# Power_Supply.net
KiCad netlist of a schematic drawn in Altium Designer
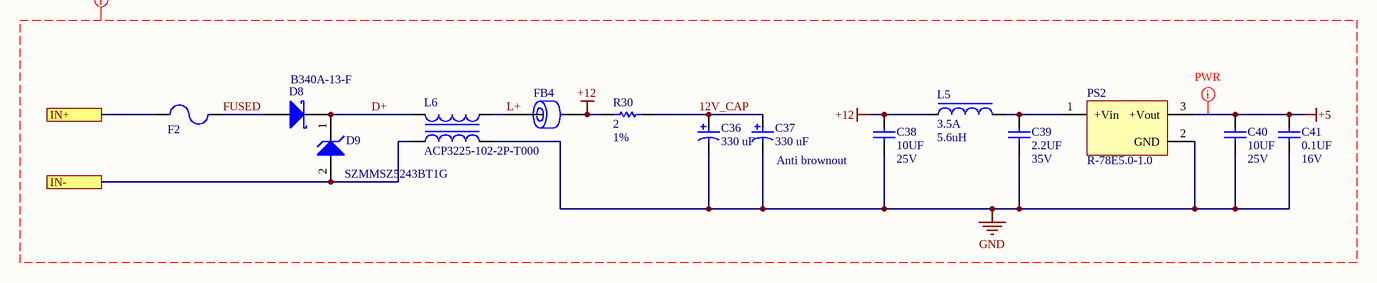
[diagram p0: Power Supply.SchDoc]

(export (version "E")
  (design (tool "Eeschema 10.0.6"))
  (components
    (comp (ref "C36")
      (value "UUD1V331MNL1GS")
      (footprint "NIC-CAPA2-10X10_V")
      (fields (field (name "MANUFACTURER") "Nichicon") (field (name "RATED CAPACITANCE") "330 uF"))
      (libsource (lib "AERO Parts") (part "UUD1V331MNL1GS"))
    )
    (comp (ref "C37")
      (value "UUD1V331MNL1GS")
      (footprint "NIC-CAPA2-10X10_V")
      (fields (field (name "MANUFACTURER") "Nichicon") (field (name "RATED CAPACITANCE") "330 uF"))
      (libsource (lib "AERO Parts") (part "UUD1V331MNL1GS"))
    )
    (comp (ref "C38")
      (value "CAP 0603 10UF 25V 20% X5R")
      (footprint "0603_CAP")
      (description "Capacitor Surface Mount 0603 Footprint 10UF 25V 20% Tolerance Ceramic X5R")
      (fields
        (field (name "VAL") "10UF")
        (field (name "VOL") "25V")
        (field (name "MANUFACTURER") "Various")
        (field (name "VOLTAGE") "25V")
      )
      (libsource (lib "Passive Components") (part "cap"))
    )
    (comp (ref "C39")
      (value "CAP 0603 2.2UF 35V 10% X5R")
      (footprint "0603_CAP")
      (description "Capacitor Surface Mount 0603 Footprint 2.2UF 35V 10% Tolerance Ceramic X5R")
      (fields
        (field (name "VAL") "2.2UF")
        (field (name "VOL") "35V")
        (field (name "MANUFACTURER") "Various")
        (field (name "VOLTAGE") "35V")
      )
      (libsource (lib "Passive Components") (part "cap"))
    )
    (comp (ref "C40")
      (value "CAP 0603 10UF 25V 20% X5R")
      (footprint "0603_CAP")
      (description "Capacitor Surface Mount 0603 Footprint 10UF 25V 20% Tolerance Ceramic X5R")
      (fields
        (field (name "VAL") "10UF")
        (field (name "VOL") "25V")
        (field (name "MANUFACTURER") "Various")
        (field (name "VOLTAGE") "25V")
      )
      (libsource (lib "Passive Components") (part "cap"))
    )
    (comp (ref "C41")
      (value "CAP 0603 0.1UF 16V 10% X7R")
      (footprint "0603_CAP")
      (description "Capacitor Surface Mount 0603 Footprint 0.1UF 16V 10% Tolerance Ceramic X7R")
      (fields
        (field (name "VAL") "0.1UF")
        (field (name "VOL") "16V")
        (field (name "MANUFACTURER") "Various")
        (field (name "VOLTAGE") "16V")
      )
      (libsource (lib "Passive Components") (part "cap"))
    )
    (comp (ref "D8")
      (value "B340A-13-F")
      (footprint "DIOD-SMA-2_V")
      (libsource (lib "Altium Content Vault") (part "DSKY-AK-2"))
    )
    (comp (ref "D9")
      (value "SZMMSZ5243BT1G")
      (footprint "ONSC-SOD-123-2-425-04_V")
      (description "Zener Voltage Regulator, 500 mW, 2-Pin SOD-123, Pb-Free, Tape and Reel")
      (fields (field (name "MANUFACTURER") "On Semiconductor"))
      (libsource (lib "Altium Content Vault") (part "ONSC-K1A2-2"))
    )
    (comp (ref "F2")
      (value "500 mA PTC")
      (footprint "1812RF")
      (description "500 mA 15 VDC PTC resettable fuse 1812 footprint")
      (fields (field (name "MANUFACTURER") "Bourns"))
      (libsource (lib "Passive Components") (part "fuse"))
    )
    (comp (ref "FB4")
      (value "Ferrite Chip 1500 Ohms")
      (footprint "0805")
      (description "Ferrite Chip 1000 mA 1500 Ohms Differential Mode - Single 0805 Footprint")
      (fields (field (name "MANUFACTURER") "Wurth Electronics"))
      (libsource (lib "Passive Components") (part "Ferrite Bead"))
    )
    (comp (ref "L5")
      (value "B1047AS-5R6N=P3")
      (footprint "B1047AS-5R6N=P3")
      (description "5.6µH Shielded Wirewound Inductor 3.5A 32mOhm Max Nonstandard")
      (fields
        (field (name "MANUFACTURER") "Murata")
        (field (name "TOLERANCE") "30%")
        (field (name "CURRENT RATING") "3.5A")
        (field (name "INDUCTANCE") "5.6uH")
      )
      (libsource (lib "AERO Parts") (part "B1047AS-5R6N=P3"))
    )
    (comp (ref "L6")
      (value "ACP3225-102-2P-T000")
      (footprint "TDK-ACP3225-102-2P-T000-4_V")
      (fields (field (name "MANUFACTURER") "TDK"))
      (libsource (lib "AERO Parts") (part "ACP3225-102-2P-T000"))
    )
    (comp (ref "PS2")
      (value "R-78E5.0-1.0")
      (footprint "R-78E5.0")
      (description "Linear Regulator Replacement DC DC Converter 1 Output 5V    1A 8V - 28V Input")
      (fields (field (name "MANUFACTURER") "Recom"))
      (libsource (lib "AERO Parts") (part "R-78E5.0-1.0"))
    )
    (comp (ref "R30")
      (value "RES 0805 2 1%")
      (footprint "0805_RES")
      (description "Resistor Surface Mount, 2 Ohms, 0805 Footprint, 1% Tolerance 0.125W")
      (fields
        (field (name "VAL") "2")
        (field (name "TOL") "1%")
        (field (name "MANUFACTURER") "Various")
        (field (name "TOLERANCE") "1%")
      )
      (libsource (lib "Passive Components") (part "res"))
    )
  )
  (nets
    (net (code "1") (name "+5") (class "Default")
      (node (ref "C40") (pin "2") (pinfunction "2_2") (pintype "passive"))
      (node (ref "C41") (pin "2") (pinfunction "2_2") (pintype "passive"))
      (node (ref "PS2") (pin "3") (pinfunction "+Vout_3") (pintype "power_in"))
    )
    (net (code "2") (name "+12") (class "Default")
      (node (ref "C38") (pin "2") (pinfunction "2_2") (pintype "passive"))
      (node (ref "FB4") (pin "2") (pinfunction "2_2") (pintype "passive"))
      (node (ref "L5") (pin "1") (pinfunction "1_1") (pintype "passive"))
      (node (ref "R30") (pin "1") (pinfunction "1_1") (pintype "passive"))
    )
    (net (code "3") (name "/12V_CAP") (class "Default")
      (node (ref "C36") (pin "1") (pinfunction "1_1") (pintype "passive"))
      (node (ref "C37") (pin "1") (pinfunction "1_1") (pintype "passive"))
      (node (ref "R30") (pin "2") (pinfunction "2_2") (pintype "passive"))
    )
    (net (code "4") (name "/D+") (class "Default")
      (node (ref "D8") (pin "2") (pinfunction "K_2") (pintype "passive"))
      (node (ref "D9") (pin "1") (pinfunction "K_1") (pintype "passive"))
      (node (ref "L6") (pin "2") (pinfunction "2_2") (pintype "passive"))
    )
    (net (code "5") (name "/FUSED") (class "Default")
      (node (ref "D8") (pin "1") (pinfunction "A_1") (pintype "passive"))
      (node (ref "F2") (pin "2") (pinfunction "2_2") (pintype "passive"))
    )
    (net (code "6") (name "/IN+") (class "Default")
      (node (ref "F2") (pin "1") (pinfunction "1_1") (pintype "passive"))
    )
    (net (code "7") (name "/IN-") (class "Default")
      (node (ref "D9") (pin "2") (pinfunction "A_2") (pintype "passive"))
      (node (ref "L6") (pin "1") (pinfunction "1_1") (pintype "passive"))
    )
    (net (code "8") (name "/L+") (class "Default")
      (node (ref "FB4") (pin "1") (pinfunction "1_1") (pintype "passive"))
      (node (ref "L6") (pin "3") (pinfunction "3_3") (pintype "passive"))
    )
    (net (code "9") (name "GND") (class "Default")
      (node (ref "C36") (pin "2") (pinfunction "2_2") (pintype "passive"))
      (node (ref "C37") (pin "2") (pinfunction "2_2") (pintype "passive"))
      (node (ref "C38") (pin "1") (pinfunction "1_1") (pintype "passive"))
      (node (ref "C39") (pin "1") (pinfunction "1_1") (pintype "passive"))
      (node (ref "C40") (pin "1") (pinfunction "1_1") (pintype "passive"))
      (node (ref "C41") (pin "1") (pinfunction "1_1") (pintype "passive"))
      (node (ref "L6") (pin "4") (pinfunction "4_4") (pintype "passive"))
      (node (ref "PS2") (pin "2") (pinfunction "GND_2") (pintype "power_in"))
    )
    (net (code "10") (name "Net-(PS2-+Vin)") (class "Default")
      (node (ref "C39") (pin "2") (pinfunction "2_2") (pintype "passive"))
      (node (ref "L5") (pin "2") (pinfunction "2_2") (pintype "passive"))
      (node (ref "PS2") (pin "1") (pinfunction "+Vin_1") (pintype "power_in"))
    )
  )
)
